# untitled.net
KiCad netlist of a schematic drawn in EAGLE
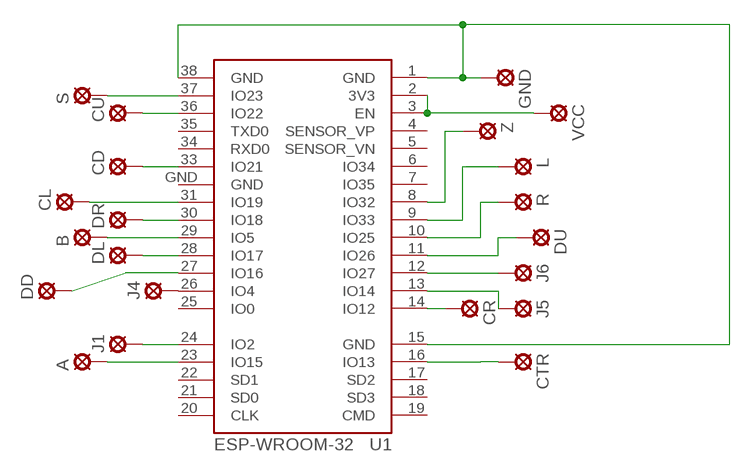
[diagram p0: schematic, sheet 1]

(export (version "E")
  (design (tool "Eeschema 10.0.6"))
  (components
    (comp (ref "A")
      (value "LSP13")
      (footprint "eagle-import:LSP13")
      (libsource (lib "eagle-import") (part "LSP13"))
    )
    (comp (ref "B")
      (value "LSP13")
      (footprint "eagle-import:LSP13")
      (libsource (lib "eagle-import") (part "LSP13"))
    )
    (comp (ref "CD")
      (value "LSP13")
      (footprint "eagle-import:LSP13")
      (libsource (lib "eagle-import") (part "LSP13"))
    )
    (comp (ref "CL")
      (value "LSP13")
      (footprint "eagle-import:LSP13")
      (libsource (lib "eagle-import") (part "LSP13"))
    )
    (comp (ref "CR")
      (value "LSP13")
      (footprint "eagle-import:LSP13")
      (libsource (lib "eagle-import") (part "LSP13"))
    )
    (comp (ref "CTR")
      (value "LSP13")
      (footprint "eagle-import:LSP13")
      (libsource (lib "eagle-import") (part "LSP13"))
    )
    (comp (ref "CU")
      (value "LSP13")
      (footprint "eagle-import:LSP13")
      (libsource (lib "eagle-import") (part "LSP13"))
    )
    (comp (ref "DD")
      (value "LSP13")
      (footprint "eagle-import:LSP13")
      (libsource (lib "eagle-import") (part "LSP13"))
    )
    (comp (ref "DL")
      (value "LSP13")
      (footprint "eagle-import:LSP13")
      (libsource (lib "eagle-import") (part "LSP13"))
    )
    (comp (ref "DR")
      (value "LSP13")
      (footprint "eagle-import:LSP13")
      (libsource (lib "eagle-import") (part "LSP13"))
    )
    (comp (ref "DU")
      (value "LSP13")
      (footprint "eagle-import:LSP13")
      (libsource (lib "eagle-import") (part "LSP13"))
    )
    (comp (ref "GND")
      (value "LSP13")
      (footprint "eagle-import:LSP13")
      (libsource (lib "eagle-import") (part "LSP13"))
    )
    (comp (ref "J1")
      (value "LSP13")
      (footprint "eagle-import:LSP13")
      (libsource (lib "eagle-import") (part "LSP13"))
    )
    (comp (ref "J4")
      (value "LSP13")
      (footprint "eagle-import:LSP13")
      (libsource (lib "eagle-import") (part "LSP13"))
    )
    (comp (ref "J5")
      (value "LSP13")
      (footprint "eagle-import:LSP13")
      (libsource (lib "eagle-import") (part "LSP13"))
    )
    (comp (ref "J6")
      (value "LSP13")
      (footprint "eagle-import:LSP13")
      (libsource (lib "eagle-import") (part "LSP13"))
    )
    (comp (ref "L")
      (value "LSP13")
      (footprint "eagle-import:LSP13")
      (libsource (lib "eagle-import") (part "LSP13"))
    )
    (comp (ref "R")
      (value "LSP13")
      (footprint "eagle-import:LSP13")
      (libsource (lib "eagle-import") (part "LSP13"))
    )
    (comp (ref "S")
      (value "LSP13")
      (footprint "eagle-import:LSP13")
      (libsource (lib "eagle-import") (part "LSP13"))
    )
    (comp (ref "U1")
      (value "ESP-WROOM-32")
      (footprint "eagle-import:ESP-WROOM-32")
      (libsource (lib "eagle-import") (part "ESP-WROOM-32"))
    )
    (comp (ref "VCC")
      (value "LSP13")
      (footprint "eagle-import:LSP13")
      (libsource (lib "eagle-import") (part "LSP13"))
    )
    (comp (ref "Z")
      (value "LSP13")
      (footprint "eagle-import:LSP13")
      (libsource (lib "eagle-import") (part "LSP13"))
    )
  )
  (nets
    (net (code "1") (name "/GND") (class "Default")
      (node (ref "U1") (pin "GND") (pinfunction "GND_GND") (pintype "power_in"))
    )
    (net (code "2") (name "Net-(GND-PadMP)") (class "Default")
      (node (ref "GND") (pin "MP") (pinfunction "MP_MP") (pintype "passive"))
      (node (ref "U1") (pin "1") (pinfunction "GND_1") (pintype "power_in"))
      (node (ref "U1") (pin "15") (pinfunction "GND_15") (pintype "power_in"))
      (node (ref "U1") (pin "38") (pinfunction "GND_38") (pintype "power_in"))
    )
    (net (code "3") (name "Net-(U1-3V3)") (class "Default")
      (node (ref "U1") (pin "2") (pinfunction "3V3_2") (pintype "power_in"))
      (node (ref "U1") (pin "3") (pinfunction "EN_3") (pintype "input"))
      (node (ref "VCC") (pin "MP") (pinfunction "MP_MP") (pintype "passive"))
    )
    (net (code "4") (name "Net-(U1-IO2)") (class "Default")
      (node (ref "J1") (pin "MP") (pinfunction "MP_MP") (pintype "passive"))
      (node (ref "U1") (pin "24") (pinfunction "IO2_24") (pintype "bidirectional"))
    )
    (net (code "5") (name "Net-(U1-IO4)") (class "Default")
      (node (ref "J4") (pin "MP") (pinfunction "MP_MP") (pintype "passive"))
      (node (ref "U1") (pin "26") (pinfunction "IO4_26") (pintype "bidirectional"))
    )
    (net (code "6") (name "Net-(U1-IO5)") (class "Default")
      (node (ref "B") (pin "MP") (pinfunction "MP_MP") (pintype "passive"))
      (node (ref "U1") (pin "29") (pinfunction "IO5_29") (pintype "bidirectional"))
    )
    (net (code "7") (name "Net-(U1-IO12)") (class "Default")
      (node (ref "CR") (pin "MP") (pinfunction "MP_MP") (pintype "passive"))
      (node (ref "U1") (pin "14") (pinfunction "IO12_14") (pintype "bidirectional"))
    )
    (net (code "8") (name "Net-(U1-IO13)") (class "Default")
      (node (ref "CTR") (pin "MP") (pinfunction "MP_MP") (pintype "passive"))
      (node (ref "U1") (pin "16") (pinfunction "IO13_16") (pintype "bidirectional"))
    )
    (net (code "9") (name "Net-(U1-IO14)") (class "Default")
      (node (ref "J5") (pin "MP") (pinfunction "MP_MP") (pintype "passive"))
      (node (ref "U1") (pin "13") (pinfunction "IO14_13") (pintype "bidirectional"))
    )
    (net (code "10") (name "Net-(U1-IO15)") (class "Default")
      (node (ref "A") (pin "MP") (pinfunction "MP_MP") (pintype "passive"))
      (node (ref "U1") (pin "23") (pinfunction "IO15_23") (pintype "bidirectional"))
    )
    (net (code "11") (name "Net-(U1-IO16)") (class "Default")
      (node (ref "DD") (pin "MP") (pinfunction "MP_MP") (pintype "passive"))
      (node (ref "U1") (pin "27") (pinfunction "IO16_27") (pintype "bidirectional"))
    )
    (net (code "12") (name "Net-(U1-IO17)") (class "Default")
      (node (ref "DL") (pin "MP") (pinfunction "MP_MP") (pintype "passive"))
      (node (ref "U1") (pin "28") (pinfunction "IO17_28") (pintype "bidirectional"))
    )
    (net (code "13") (name "Net-(U1-IO18)") (class "Default")
      (node (ref "DR") (pin "MP") (pinfunction "MP_MP") (pintype "passive"))
      (node (ref "U1") (pin "30") (pinfunction "IO18_30") (pintype "bidirectional"))
    )
    (net (code "14") (name "Net-(U1-IO19)") (class "Default")
      (node (ref "CL") (pin "MP") (pinfunction "MP_MP") (pintype "passive"))
      (node (ref "U1") (pin "31") (pinfunction "IO19_31") (pintype "bidirectional"))
    )
    (net (code "15") (name "Net-(U1-IO21)") (class "Default")
      (node (ref "CD") (pin "MP") (pinfunction "MP_MP") (pintype "passive"))
      (node (ref "U1") (pin "33") (pinfunction "IO21_33") (pintype "bidirectional"))
    )
    (net (code "16") (name "Net-(U1-IO22)") (class "Default")
      (node (ref "CU") (pin "MP") (pinfunction "MP_MP") (pintype "passive"))
      (node (ref "U1") (pin "36") (pinfunction "IO22_36") (pintype "bidirectional"))
    )
    (net (code "17") (name "Net-(U1-IO23)") (class "Default")
      (node (ref "S") (pin "MP") (pinfunction "MP_MP") (pintype "passive"))
      (node (ref "U1") (pin "37") (pinfunction "IO23_37") (pintype "bidirectional"))
    )
    (net (code "18") (name "Net-(U1-IO25)") (class "Default")
      (node (ref "R") (pin "MP") (pinfunction "MP_MP") (pintype "passive"))
      (node (ref "U1") (pin "10") (pinfunction "IO25_10") (pintype "bidirectional"))
    )
    (net (code "19") (name "Net-(U1-IO26)") (class "Default")
      (node (ref "DU") (pin "MP") (pinfunction "MP_MP") (pintype "passive"))
      (node (ref "U1") (pin "11") (pinfunction "IO26_11") (pintype "bidirectional"))
    )
    (net (code "20") (name "Net-(U1-IO27)") (class "Default")
      (node (ref "J6") (pin "MP") (pinfunction "MP_MP") (pintype "passive"))
      (node (ref "U1") (pin "12") (pinfunction "IO27_12") (pintype "bidirectional"))
    )
    (net (code "21") (name "Net-(U1-IO32)") (class "Default")
      (node (ref "U1") (pin "8") (pinfunction "IO32_8") (pintype "bidirectional"))
      (node (ref "Z") (pin "MP") (pinfunction "MP_MP") (pintype "passive"))
    )
    (net (code "22") (name "Net-(U1-IO33)") (class "Default")
      (node (ref "L") (pin "MP") (pinfunction "MP_MP") (pintype "passive"))
      (node (ref "U1") (pin "9") (pinfunction "IO33_9") (pintype "bidirectional"))
    )
    (net (code "23") (name "unconnected-(U1-CLK-Pad20)") (class "Default")
      (node (ref "U1") (pin "20") (pinfunction "CLK_20") (pintype "bidirectional"))
    )
    (net (code "24") (name "unconnected-(U1-CMD-Pad19)") (class "Default")
      (node (ref "U1") (pin "19") (pinfunction "CMD_19") (pintype "bidirectional"))
    )
    (net (code "25") (name "unconnected-(U1-IO0-Pad25)") (class "Default")
      (node (ref "U1") (pin "25") (pinfunction "IO0_25") (pintype "bidirectional"))
    )
    (net (code "26") (name "unconnected-(U1-IO34-Pad6)") (class "Default")
      (node (ref "U1") (pin "6") (pinfunction "IO34_6") (pintype "bidirectional"))
    )
    (net (code "27") (name "unconnected-(U1-IO35-Pad7)") (class "Default")
      (node (ref "U1") (pin "7") (pinfunction "IO35_7") (pintype "bidirectional"))
    )
    (net (code "28") (name "unconnected-(U1-RXD0-Pad34)") (class "Default")
      (node (ref "U1") (pin "34") (pinfunction "RXD0_34") (pintype "bidirectional"))
    )
    (net (code "29") (name "unconnected-(U1-SD0-Pad21)") (class "Default")
      (node (ref "U1") (pin "21") (pinfunction "SD0_21") (pintype "bidirectional"))
    )
    (net (code "30") (name "unconnected-(U1-SD1-Pad22)") (class "Default")
      (node (ref "U1") (pin "22") (pinfunction "SD1_22") (pintype "bidirectional"))
    )
    (net (code "31") (name "unconnected-(U1-SD2-Pad17)") (class "Default")
      (node (ref "U1") (pin "17") (pinfunction "SD2_17") (pintype "bidirectional"))
    )
    (net (code "32") (name "unconnected-(U1-SD3-Pad18)") (class "Default")
      (node (ref "U1") (pin "18") (pinfunction "SD3_18") (pintype "bidirectional"))
    )
    (net (code "33") (name "unconnected-(U1-SENSOR_VN-Pad5)") (class "Default")
      (node (ref "U1") (pin "5") (pinfunction "SENSOR_VN_5") (pintype "bidirectional"))
    )
    (net (code "34") (name "unconnected-(U1-SENSOR_VP-Pad4)") (class "Default")
      (node (ref "U1") (pin "4") (pinfunction "SENSOR_VP_4") (pintype "bidirectional"))
    )
    (net (code "35") (name "unconnected-(U1-TXD0-Pad35)") (class "Default")
      (node (ref "U1") (pin "35") (pinfunction "TXD0_35") (pintype "bidirectional"))
    )
  )
)
